# Sheet1-control.net
KiCad netlist of a schematic drawn in Altium Designer
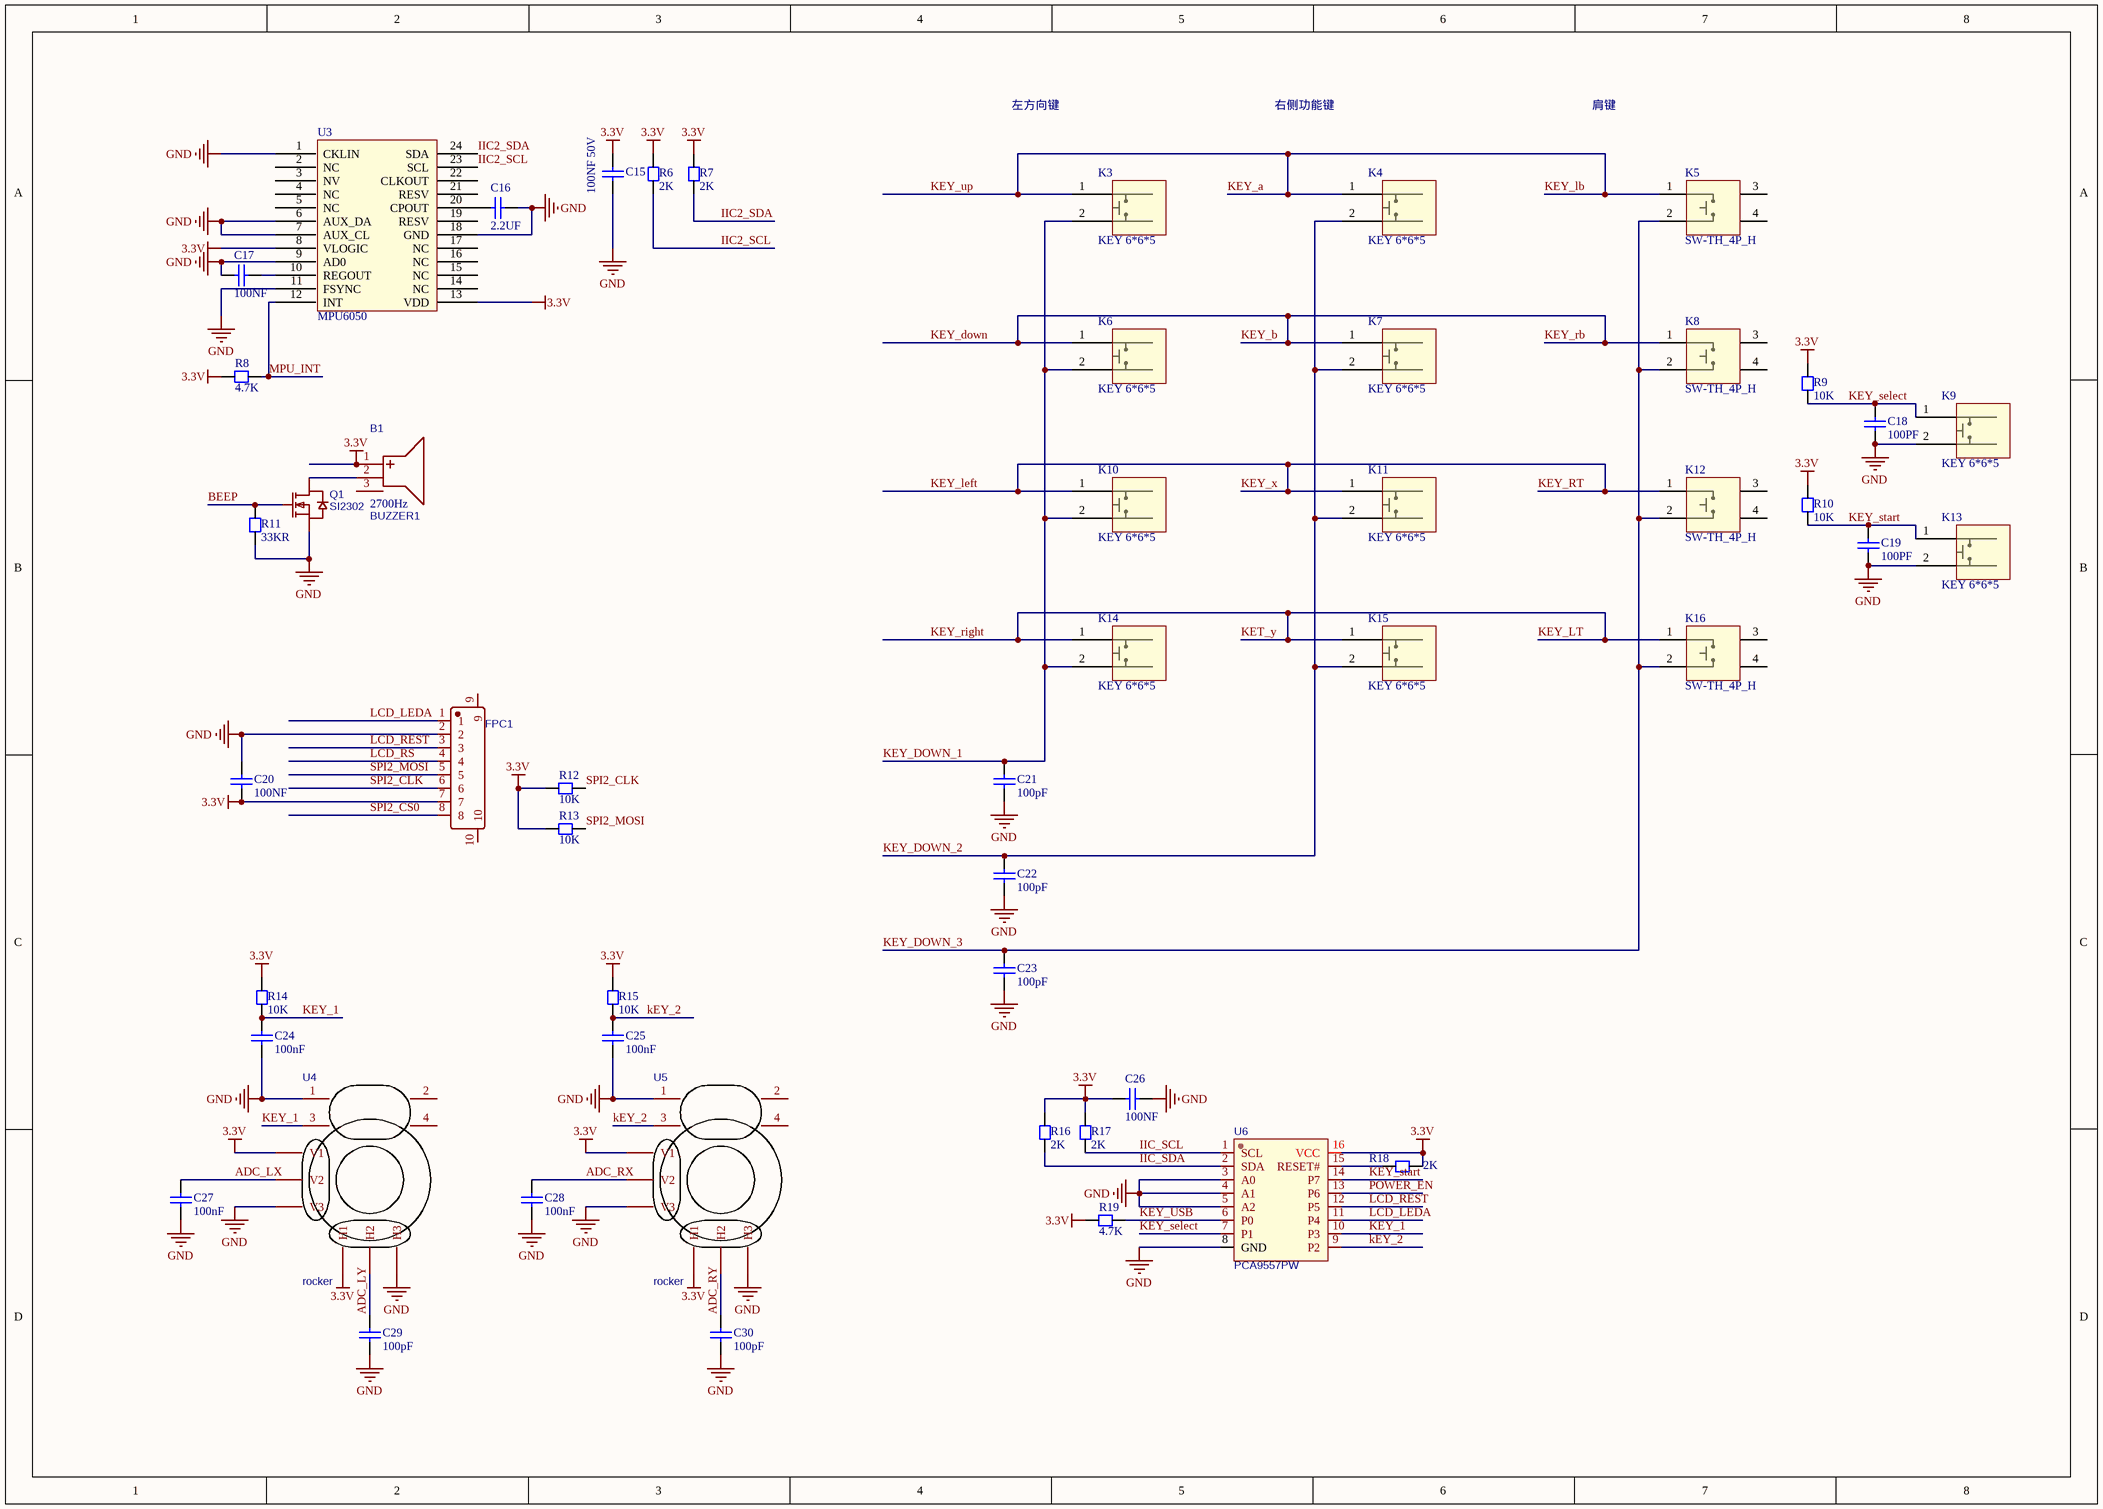
[diagram p0: Sheet1-control.SchDoc]

(export (version "E")
  (design (tool "Eeschema 10.0.6"))
  (components
    (comp (ref "B1")
      (value "BUZZER1")
      (footprint "BUZ-SMD_GSC7525RA")
      (description "2700Hz")
      (fields
        (field (name "MANUFACTURER") "INGHAi(赢海)")
        (field (name "MANUFACTURER PART") "GSC7525RA-16R2700")
        (field (name "CONTRIBUTOR") "LCSC")
      )
      (libsource (lib "base") (part "BUZZER1"))
    )
    (comp (ref "C15")
      (value "100NF 50V")
      (footprint "CC1608-0603")
      (description "0603封装的电容")
      (fields (field (name "PUBLISHER") "Altium Limited"))
      (libsource (lib "base") (part "Cap Chip 0603"))
    )
    (comp (ref "C16")
      (value "2.2UF")
      (footprint "CC1608-0603")
      (description "0603封装的电容")
      (fields (field (name "PUBLISHER") "Altium Limited"))
      (libsource (lib "base") (part "Cap Chip 0603"))
    )
    (comp (ref "C17")
      (value "100NF")
      (footprint "CC1608-0603")
      (description "0603封装的电容")
      (fields (field (name "PUBLISHER") "Altium Limited"))
      (libsource (lib "base") (part "Cap Chip 0603"))
    )
    (comp (ref "C18")
      (value "100PF")
      (footprint "CC1608-0603")
      (description "0603封装的电容")
      (fields (field (name "PUBLISHER") "Altium Limited"))
      (libsource (lib "base") (part "Cap Chip 0603"))
    )
    (comp (ref "C19")
      (value "100PF")
      (footprint "CC1608-0603")
      (description "0603封装的电容")
      (fields (field (name "PUBLISHER") "Altium Limited"))
      (libsource (lib "base") (part "Cap Chip 0603"))
    )
    (comp (ref "C20")
      (value "100NF")
      (footprint "CC1608-0603")
      (description "0603封装的电容")
      (fields (field (name "PUBLISHER") "Altium Limited"))
      (libsource (lib "base") (part "Cap Chip 0603"))
    )
    (comp (ref "C21")
      (value "100pF")
      (footprint "CC1608-0603")
      (description "0603封装的电容")
      (fields (field (name "PUBLISHER") "Altium Limited"))
      (libsource (lib "base") (part "Cap Chip 0603"))
    )
    (comp (ref "C22")
      (value "100pF")
      (footprint "CC1608-0603")
      (description "0603封装的电容")
      (fields (field (name "PUBLISHER") "Altium Limited"))
      (libsource (lib "base") (part "Cap Chip 0603"))
    )
    (comp (ref "C23")
      (value "100pF")
      (footprint "CC1608-0603")
      (description "0603封装的电容")
      (fields (field (name "PUBLISHER") "Altium Limited"))
      (libsource (lib "base") (part "Cap Chip 0603"))
    )
    (comp (ref "C24")
      (value "100nF")
      (footprint "CC1608-0603")
      (description "0603封装的电容")
      (fields (field (name "PUBLISHER") "Altium Limited"))
      (libsource (lib "base") (part "Cap Chip 0603"))
    )
    (comp (ref "C25")
      (value "100nF")
      (footprint "CC1608-0603")
      (description "0603封装的电容")
      (fields (field (name "PUBLISHER") "Altium Limited"))
      (libsource (lib "base") (part "Cap Chip 0603"))
    )
    (comp (ref "C26")
      (value "100NF")
      (footprint "CC1608-0603")
      (description "0603封装的电容")
      (fields (field (name "PUBLISHER") "Altium Limited"))
      (libsource (lib "base") (part "Cap Chip 0603"))
    )
    (comp (ref "C27")
      (value "100nF")
      (footprint "CC1608-0603")
      (description "0603封装的电容")
      (fields (field (name "PUBLISHER") "Altium Limited"))
      (libsource (lib "base") (part "Cap Chip 0603"))
    )
    (comp (ref "C28")
      (value "100nF")
      (footprint "CC1608-0603")
      (description "0603封装的电容")
      (fields (field (name "PUBLISHER") "Altium Limited"))
      (libsource (lib "base") (part "Cap Chip 0603"))
    )
    (comp (ref "C29")
      (value "100pF")
      (footprint "CC1608-0603")
      (description "0603封装的电容")
      (fields (field (name "PUBLISHER") "Altium Limited"))
      (libsource (lib "base") (part "Cap Chip 0603"))
    )
    (comp (ref "C30")
      (value "100pF")
      (footprint "CC1608-0603")
      (description "0603封装的电容")
      (fields (field (name "PUBLISHER") "Altium Limited"))
      (libsource (lib "base") (part "Cap Chip 0603"))
    )
    (comp (ref "FPC1")
      (value "FFC 05 8P")
      (footprint "FFC-SMD_8P-P0.50")
      (fields
        (field (name "MANUFACTURER") "TXGA(特思嘉)")
        (field (name "MANUFACTURER PART") "FFC05001-08SBB124W5M-H")
        (field (name "CONTRIBUTOR") "LCSC")
      )
      (libsource (lib "Connectors") (part "FFC 05 8P"))
    )
    (comp (ref "K3")
      (value "KEY 6*6*5")
      (footprint "KEY 6*6*5")
      (description "无声轻触开关")
      (libsource (lib "base") (part "KEY 6*6*5"))
    )
    (comp (ref "K4")
      (value "KEY 6*6*5")
      (footprint "KEY 6*6*5")
      (description "无声轻触开关")
      (libsource (lib "base") (part "KEY 6*6*5"))
    )
    (comp (ref "K5")
      (value "SW-TH_4P_H")
      (footprint "SW-TH_KH-6X6X7H-ZJ")
      (description "卧式轻触开关")
      (libsource (lib "base") (part "SW-TH_4P_H"))
    )
    (comp (ref "K6")
      (value "KEY 6*6*5")
      (footprint "KEY 6*6*5")
      (description "无声轻触开关")
      (libsource (lib "base") (part "KEY 6*6*5"))
    )
    (comp (ref "K7")
      (value "KEY 6*6*5")
      (footprint "KEY 6*6*5")
      (description "无声轻触开关")
      (libsource (lib "base") (part "KEY 6*6*5"))
    )
    (comp (ref "K8")
      (value "SW-TH_4P_H")
      (footprint "SW-TH_KH-6X6X7H-ZJ")
      (description "卧式轻触开关")
      (libsource (lib "base") (part "SW-TH_4P_H"))
    )
    (comp (ref "K9")
      (value "KEY 6*6*5")
      (footprint "KEY 6*6*5")
      (description "无声轻触开关")
      (libsource (lib "base") (part "KEY 6*6*5"))
    )
    (comp (ref "K10")
      (value "KEY 6*6*5")
      (footprint "KEY 6*6*5")
      (description "无声轻触开关")
      (libsource (lib "base") (part "KEY 6*6*5"))
    )
    (comp (ref "K11")
      (value "KEY 6*6*5")
      (footprint "KEY 6*6*5")
      (description "无声轻触开关")
      (libsource (lib "base") (part "KEY 6*6*5"))
    )
    (comp (ref "K12")
      (value "SW-TH_4P_H")
      (footprint "SW-TH_KH-6X6X7H-ZJ")
      (description "卧式轻触开关")
      (libsource (lib "base") (part "SW-TH_4P_H"))
    )
    (comp (ref "K13")
      (value "KEY 6*6*5")
      (footprint "KEY 6*6*5")
      (description "无声轻触开关")
      (libsource (lib "base") (part "KEY 6*6*5"))
    )
    (comp (ref "K14")
      (value "KEY 6*6*5")
      (footprint "KEY 6*6*5")
      (description "无声轻触开关")
      (libsource (lib "base") (part "KEY 6*6*5"))
    )
    (comp (ref "K15")
      (value "KEY 6*6*5")
      (footprint "KEY 6*6*5")
      (description "无声轻触开关")
      (libsource (lib "base") (part "KEY 6*6*5"))
    )
    (comp (ref "K16")
      (value "SW-TH_4P_H")
      (footprint "SW-TH_KH-6X6X7H-ZJ")
      (description "卧式轻触开关")
      (libsource (lib "base") (part "SW-TH_4P_H"))
    )
    (comp (ref "Q1")
      (value "SI2302")
      (footprint "SOT-23")
      (fields
        (field (name "MANUFACTURER") "TWGMC(台湾迪嘉)")
        (field (name "MANUFACTURER PART") "SI2306")
        (field (name "CONTRIBUTOR") "LCSC")
      )
      (libsource (lib "transistor") (part "SI2302"))
    )
    (comp (ref "R6")
      (value "2K")
      (footprint "CR1608-0603")
      (description "0603封装电阻")
      (fields (field (name "PUBLISHER") "Altium Limited"))
      (libsource (lib "") (part "Resistor Chip 0603_1"))
    )
    (comp (ref "R7")
      (value "2K")
      (footprint "CR1608-0603")
      (description "0603封装电阻")
      (fields (field (name "PUBLISHER") "Altium Limited"))
      (libsource (lib "") (part "Resistor Chip 0603_1"))
    )
    (comp (ref "R8")
      (value "4.7K")
      (footprint "CR1608-0603")
      (description "0603封装电阻")
      (fields (field (name "PUBLISHER") "Altium Limited"))
      (libsource (lib "") (part "Resistor Chip 0603_2"))
    )
    (comp (ref "R9")
      (value "10K")
      (footprint "CR1608-0603")
      (description "0603封装电阻")
      (fields (field (name "PUBLISHER") "Altium Limited"))
      (libsource (lib "") (part "Resistor Chip 0603_1"))
    )
    (comp (ref "R10")
      (value "10K")
      (footprint "CR1608-0603")
      (description "0603封装电阻")
      (fields (field (name "PUBLISHER") "Altium Limited"))
      (libsource (lib "") (part "Resistor Chip 0603_1"))
    )
    (comp (ref "R11")
      (value "33KR")
      (footprint "CR1608-0603")
      (description "贴片电阻")
      (libsource (lib "tianxiaohua_Schlib") (part "Chip resistor"))
    )
    (comp (ref "R12")
      (value "10K")
      (footprint "CR1608-0603")
      (description "0603封装电阻")
      (fields (field (name "PUBLISHER") "Altium Limited"))
      (libsource (lib "base") (part "Resistor Chip 0603"))
    )
    (comp (ref "R13")
      (value "10K")
      (footprint "CR1608-0603")
      (description "0603封装电阻")
      (fields (field (name "PUBLISHER") "Altium Limited"))
      (libsource (lib "base") (part "Resistor Chip 0603"))
    )
    (comp (ref "R14")
      (value "10K")
      (footprint "CR1608-0603")
      (description "0603封装电阻")
      (fields (field (name "PUBLISHER") "Altium Limited"))
      (libsource (lib "") (part "Resistor Chip 0603_3"))
    )
    (comp (ref "R15")
      (value "10K")
      (footprint "CR1608-0603")
      (description "0603封装电阻")
      (fields (field (name "PUBLISHER") "Altium Limited"))
      (libsource (lib "") (part "Resistor Chip 0603_3"))
    )
    (comp (ref "R16")
      (value "2K")
      (footprint "CR1608-0603")
      (description "0603封装电阻")
      (fields (field (name "PUBLISHER") "Altium Limited"))
      (libsource (lib "") (part "Resistor Chip 0603_1"))
    )
    (comp (ref "R17")
      (value "2K")
      (footprint "CR1608-0603")
      (description "0603封装电阻")
      (fields (field (name "PUBLISHER") "Altium Limited"))
      (libsource (lib "") (part "Resistor Chip 0603_1"))
    )
    (comp (ref "R18")
      (value "2K")
      (footprint "CR1608-0603")
      (description "0603封装电阻")
      (fields (field (name "PUBLISHER") "Altium Limited"))
      (libsource (lib "base") (part "Resistor Chip 0603"))
    )
    (comp (ref "R19")
      (value "4.7K")
      (footprint "CR1608-0603")
      (description "0603封装电阻")
      (fields (field (name "PUBLISHER") "Altium Limited"))
      (libsource (lib "") (part "Resistor Chip 0603_2"))
    )
    (comp (ref "U3")
      (value "MPU6050")
      (footprint "QFN24 - duplicate")
      (description "陀螺仪")
      (libsource (lib "sensor") (part "MPU6050"))
    )
    (comp (ref "U4")
      (value "rocker")
      (footprint "PCBComponent_1")
      (fields (field (name "MANUFACTURER PART") "摇杆") (field (name "CONTRIBUTOR") "Alex_Ai"))
      (libsource (lib "base") (part "rocker"))
    )
    (comp (ref "U5")
      (value "rocker")
      (footprint "PCBComponent_1")
      (fields (field (name "MANUFACTURER PART") "摇杆") (field (name "CONTRIBUTOR") "Alex_Ai"))
      (libsource (lib "base") (part "rocker"))
    )
    (comp (ref "U6")
      (value "PCA9557PW")
      (footprint "TSSOP-16")
      (description "TSSOP-16 8位I2C总线和SMBus I/O扩展器芯片")
      (fields (field (name "MANUFACTURER") "TI(德州仪器)") (field (name "CONTRIBUTOR") "LCSC"))
      (libsource (lib "PB-Chip") (part "PCA9557PW"))
    )
  )
  (nets
    (net (code "1") (name "/ADC_LX") (class "Default")
      (node (ref "C27") (pin "2") (pinfunction "2_2") (pintype "passive"))
      (node (ref "U4") (pin "6") (pinfunction "V2_6") (pintype "passive"))
    )
    (net (code "2") (name "/ADC_LY") (class "Default")
      (node (ref "C29") (pin "2") (pinfunction "2_2") (pintype "passive"))
      (node (ref "U4") (pin "9") (pinfunction "H2_9") (pintype "passive"))
    )
    (net (code "3") (name "/ADC_RX") (class "Default")
      (node (ref "C28") (pin "2") (pinfunction "2_2") (pintype "passive"))
      (node (ref "U5") (pin "6") (pinfunction "V2_6") (pintype "passive"))
    )
    (net (code "4") (name "/ADC_RY") (class "Default")
      (node (ref "C30") (pin "2") (pinfunction "2_2") (pintype "passive"))
      (node (ref "U5") (pin "9") (pinfunction "H2_9") (pintype "passive"))
    )
    (net (code "5") (name "/BEEP") (class "Default")
      (node (ref "Q1") (pin "1") (pinfunction "G_1") (pintype "passive"))
      (node (ref "R11") (pin "1") (pinfunction "1_1") (pintype "passive"))
    )
    (net (code "6") (name "/IIC2_SCL") (class "Default")
      (node (ref "R6") (pin "2") (pinfunction "2_2") (pintype "passive"))
      (node (ref "U3") (pin "23") (pinfunction "SCL_23") (pintype "passive"))
    )
    (net (code "7") (name "/IIC2_SDA") (class "Default")
      (node (ref "R7") (pin "2") (pinfunction "2_2") (pintype "passive"))
      (node (ref "U3") (pin "24") (pinfunction "SDA_24") (pintype "passive"))
    )
    (net (code "8") (name "/IIC_SCL") (class "Default")
      (node (ref "R17") (pin "2") (pinfunction "2_2") (pintype "passive"))
      (node (ref "U6") (pin "1") (pinfunction "SCL_1") (pintype "passive"))
    )
    (net (code "9") (name "/IIC_SDA") (class "Default")
      (node (ref "R16") (pin "2") (pinfunction "2_2") (pintype "passive"))
      (node (ref "U6") (pin "2") (pinfunction "SDA_2") (pintype "passive"))
    )
    (net (code "10") (name "/KET_y") (class "Default")
      (node (ref "K14") (pin "1") (pinfunction "1_1") (pintype "passive"))
      (node (ref "K15") (pin "1") (pinfunction "1_1") (pintype "passive"))
      (node (ref "K16") (pin "1") (pinfunction "1_1") (pintype "passive"))
    )
    (net (code "11") (name "/KEY_1") (class "Default")
      (node (ref "C24") (pin "2") (pinfunction "2_2") (pintype "passive"))
      (node (ref "R14") (pin "1") (pinfunction "1_1") (pintype "passive"))
      (node (ref "U4") (pin "3") (pinfunction "3_3") (pintype "passive"))
      (node (ref "U6") (pin "10") (pinfunction "P3_10") (pintype "passive"))
    )
    (net (code "12") (name "/KEY_DOWN_1") (class "Default")
      (node (ref "C21") (pin "2") (pinfunction "2_2") (pintype "passive"))
      (node (ref "K10") (pin "2") (pinfunction "2_2") (pintype "passive"))
      (node (ref "K14") (pin "2") (pinfunction "2_2") (pintype "passive"))
      (node (ref "K3") (pin "2") (pinfunction "2_2") (pintype "passive"))
      (node (ref "K6") (pin "2") (pinfunction "2_2") (pintype "passive"))
    )
    (net (code "13") (name "/KEY_DOWN_2") (class "Default")
      (node (ref "C22") (pin "2") (pinfunction "2_2") (pintype "passive"))
      (node (ref "K11") (pin "2") (pinfunction "2_2") (pintype "passive"))
      (node (ref "K15") (pin "2") (pinfunction "2_2") (pintype "passive"))
      (node (ref "K4") (pin "2") (pinfunction "2_2") (pintype "passive"))
      (node (ref "K7") (pin "2") (pinfunction "2_2") (pintype "passive"))
    )
    (net (code "14") (name "/KEY_DOWN_3") (class "Default")
      (node (ref "C23") (pin "2") (pinfunction "2_2") (pintype "passive"))
      (node (ref "K12") (pin "2") (pinfunction "2_2") (pintype "passive"))
      (node (ref "K16") (pin "2") (pinfunction "2_2") (pintype "passive"))
      (node (ref "K5") (pin "2") (pinfunction "2_2") (pintype "passive"))
      (node (ref "K8") (pin "2") (pinfunction "2_2") (pintype "passive"))
    )
    (net (code "15") (name "/KEY_RT") (class "Default")
      (node (ref "K10") (pin "1") (pinfunction "1_1") (pintype "passive"))
      (node (ref "K11") (pin "1") (pinfunction "1_1") (pintype "passive"))
      (node (ref "K12") (pin "1") (pinfunction "1_1") (pintype "passive"))
    )
    (net (code "16") (name "/KEY_USB") (class "Default")
      (node (ref "R19") (pin "2") (pinfunction "2_2") (pintype "passive"))
      (node (ref "U6") (pin "6") (pinfunction "P0_6") (pintype "passive"))
    )
    (net (code "17") (name "/KEY_a") (class "Default")
      (node (ref "K3") (pin "1") (pinfunction "1_1") (pintype "passive"))
      (node (ref "K4") (pin "1") (pinfunction "1_1") (pintype "passive"))
      (node (ref "K5") (pin "1") (pinfunction "1_1") (pintype "passive"))
    )
    (net (code "18") (name "/KEY_b") (class "Default")
      (node (ref "K6") (pin "1") (pinfunction "1_1") (pintype "passive"))
      (node (ref "K7") (pin "1") (pinfunction "1_1") (pintype "passive"))
      (node (ref "K8") (pin "1") (pinfunction "1_1") (pintype "passive"))
    )
    (net (code "19") (name "/KEY_select") (class "Default")
      (node (ref "C18") (pin "1") (pinfunction "1_1") (pintype "passive"))
      (node (ref "K9") (pin "1") (pinfunction "1_1") (pintype "passive"))
      (node (ref "R9") (pin "2") (pinfunction "2_2") (pintype "passive"))
      (node (ref "U6") (pin "7") (pinfunction "P1_7") (pintype "passive"))
    )
    (net (code "20") (name "/KEY_start") (class "Default")
      (node (ref "C19") (pin "1") (pinfunction "1_1") (pintype "passive"))
      (node (ref "K13") (pin "1") (pinfunction "1_1") (pintype "passive"))
      (node (ref "R10") (pin "2") (pinfunction "2_2") (pintype "passive"))
      (node (ref "U6") (pin "14") (pinfunction "P7_14") (pintype "passive"))
    )
    (net (code "21") (name "/LCD_LEDA") (class "Default")
      (node (ref "FPC1") (pin "1") (pinfunction "1_1") (pintype "passive"))
      (node (ref "U6") (pin "11") (pinfunction "P4_11") (pintype "passive"))
    )
    (net (code "22") (name "/LCD_REST") (class "Default")
      (node (ref "FPC1") (pin "3") (pinfunction "3_3") (pintype "passive"))
      (node (ref "U6") (pin "12") (pinfunction "P5_12") (pintype "passive"))
    )
    (net (code "23") (name "/LCD_RS") (class "Default")
      (node (ref "FPC1") (pin "4") (pinfunction "4_4") (pintype "passive"))
    )
    (net (code "24") (name "/MPU_INT") (class "Default")
      (node (ref "R8") (pin "2") (pinfunction "2_2") (pintype "passive"))
      (node (ref "U3") (pin "12") (pinfunction "INT_12") (pintype "passive"))
    )
    (net (code "25") (name "/POWER_EN") (class "Default")
      (node (ref "U6") (pin "13") (pinfunction "P6_13") (pintype "passive"))
    )
    (net (code "26") (name "/SPI2_CLK") (class "Default")
      (node (ref "FPC1") (pin "6") (pinfunction "6_6") (pintype "passive"))
      (node (ref "R12") (pin "1") (pinfunction "1_1") (pintype "passive"))
    )
    (net (code "27") (name "/SPI2_CS0") (class "Default")
      (node (ref "FPC1") (pin "8") (pinfunction "8_8") (pintype "passive"))
    )
    (net (code "28") (name "/SPI2_MOSI") (class "Default")
      (node (ref "FPC1") (pin "5") (pinfunction "5_5") (pintype "passive"))
      (node (ref "R13") (pin "1") (pinfunction "1_1") (pintype "passive"))
    )
    (net (code "29") (name "/kEY_2") (class "Default")
      (node (ref "C25") (pin "2") (pinfunction "2_2") (pintype "passive"))
      (node (ref "R15") (pin "1") (pinfunction "1_1") (pintype "passive"))
      (node (ref "U5") (pin "3") (pinfunction "3_3") (pintype "passive"))
      (node (ref "U6") (pin "9") (pinfunction "P2_9") (pintype "passive"))
    )
    (net (code "30") (name "3.3V") (class "Default")
      (node (ref "B1") (pin "1") (pinfunction "+_1") (pintype "passive"))
      (node (ref "C15") (pin "2") (pinfunction "2_2") (pintype "passive"))
      (node (ref "C20") (pin "1") (pinfunction "1_1") (pintype "passive"))
      (node (ref "C26") (pin "2") (pinfunction "2_2") (pintype "passive"))
      (node (ref "FPC1") (pin "7") (pinfunction "7_7") (pintype "passive"))
      (node (ref "R10") (pin "1") (pinfunction "1_1") (pintype "passive"))
      (node (ref "R12") (pin "2") (pinfunction "2_2") (pintype "passive"))
      (node (ref "R13") (pin "2") (pinfunction "2_2") (pintype "passive"))
      (node (ref "R14") (pin "2") (pinfunction "2_2") (pintype "passive"))
      (node (ref "R15") (pin "2") (pinfunction "2_2") (pintype "passive"))
      (node (ref "R16") (pin "1") (pinfunction "1_1") (pintype "passive"))
      (node (ref "R17") (pin "1") (pinfunction "1_1") (pintype "passive"))
      (node (ref "R18") (pin "1") (pinfunction "1_1") (pintype "passive"))
      (node (ref "R19") (pin "1") (pinfunction "1_1") (pintype "passive"))
      (node (ref "R6") (pin "1") (pinfunction "1_1") (pintype "passive"))
      (node (ref "R7") (pin "1") (pinfunction "1_1") (pintype "passive"))
      (node (ref "R8") (pin "1") (pinfunction "1_1") (pintype "passive"))
      (node (ref "R9") (pin "1") (pinfunction "1_1") (pintype "passive"))
      (node (ref "U3") (pin "13") (pinfunction "VDD_13") (pintype "passive"))
      (node (ref "U3") (pin "8") (pinfunction "VLOGIC_8") (pintype "passive"))
      (node (ref "U4") (pin "5") (pinfunction "V1_5") (pintype "passive"))
      (node (ref "U4") (pin "8") (pinfunction "H1_8") (pintype "passive"))
      (node (ref "U5") (pin "5") (pinfunction "V1_5") (pintype "passive"))
      (node (ref "U5") (pin "8") (pinfunction "H1_8") (pintype "passive"))
      (node (ref "U6") (pin "16") (pinfunction "VCC_16") (pintype "passive"))
    )
    (net (code "31") (name "GND") (class "Default")
      (node (ref "C15") (pin "1") (pinfunction "1_1") (pintype "passive"))
      (node (ref "C16") (pin "2") (pinfunction "2_2") (pintype "passive"))
      (node (ref "C17") (pin "1") (pinfunction "1_1") (pintype "passive"))
      (node (ref "C18") (pin "2") (pinfunction "2_2") (pintype "passive"))
      (node (ref "C19") (pin "2") (pinfunction "2_2") (pintype "passive"))
      (node (ref "C20") (pin "2") (pinfunction "2_2") (pintype "passive"))
      (node (ref "C21") (pin "1") (pinfunction "1_1") (pintype "passive"))
      (node (ref "C22") (pin "1") (pinfunction "1_1") (pintype "passive"))
      (node (ref "C23") (pin "1") (pinfunction "1_1") (pintype "passive"))
      (node (ref "C24") (pin "1") (pinfunction "1_1") (pintype "passive"))
      (node (ref "C25") (pin "1") (pinfunction "1_1") (pintype "passive"))
      (node (ref "C26") (pin "1") (pinfunction "1_1") (pintype "passive"))
      (node (ref "C27") (pin "1") (pinfunction "1_1") (pintype "passive"))
      (node (ref "C28") (pin "1") (pinfunction "1_1") (pintype "passive"))
      (node (ref "C29") (pin "1") (pinfunction "1_1") (pintype "passive"))
      (node (ref "C30") (pin "1") (pinfunction "1_1") (pintype "passive"))
      (node (ref "FPC1") (pin "2") (pinfunction "2_2") (pintype "passive"))
      (node (ref "K13") (pin "2") (pinfunction "2_2") (pintype "passive"))
      (node (ref "K9") (pin "2") (pinfunction "2_2") (pintype "passive"))
      (node (ref "Q1") (pin "2") (pinfunction "S_2") (pintype "passive"))
      (node (ref "R11") (pin "2") (pinfunction "2_2") (pintype "passive"))
      (node (ref "U3") (pin "1") (pinfunction "CKLIN_1") (pintype "passive"))
      (node (ref "U3") (pin "11") (pinfunction "FSYNC_11") (pintype "passive"))
      (node (ref "U3") (pin "18") (pinfunction "GND_18") (pintype "passive"))
      (node (ref "U3") (pin "6") (pinfunction "AUX_DA_6") (pintype "passive"))
      (node (ref "U3") (pin "7") (pinfunction "AUX_CL_7") (pintype "passive"))
      (node (ref "U3") (pin "9") (pinfunction "AD0_9") (pintype "passive"))
      (node (ref "U4") (pin "1") (pinfunction "1_1") (pintype "passive"))
      (node (ref "U4") (pin "10") (pinfunction "H3_10") (pintype "passive"))
      (node (ref "U4") (pin "7") (pinfunction "V3_7") (pintype "passive"))
      (node (ref "U5") (pin "1") (pinfunction "1_1") (pintype "passive"))
      (node (ref "U5") (pin "10") (pinfunction "H3_10") (pintype "passive"))
      (node (ref "U5") (pin "7") (pinfunction "V3_7") (pintype "passive"))
      (node (ref "U6") (pin "3") (pinfunction "A0_3") (pintype "passive"))
      (node (ref "U6") (pin "4") (pinfunction "A1_4") (pintype "passive"))
      (node (ref "U6") (pin "5") (pinfunction "A2_5") (pintype "passive"))
      (node (ref "U6") (pin "8") (pinfunction "GND_8") (pintype "passive"))
    )
    (net (code "32") (name "Net-(B1--)") (class "Default")
      (node (ref "B1") (pin "2") (pinfunction "-_2") (pintype "passive"))
      (node (ref "Q1") (pin "3") (pinfunction "D_3") (pintype "passive"))
    )
    (net (code "33") (name "Net-(U3-CPOUT)") (class "Default")
      (node (ref "C16") (pin "1") (pinfunction "1_1") (pintype "passive"))
      (node (ref "U3") (pin "20") (pinfunction "CPOUT_20") (pintype "passive"))
    )
    (net (code "34") (name "Net-(U3-REGOUT)") (class "Default")
      (node (ref "C17") (pin "2") (pinfunction "2_2") (pintype "passive"))
      (node (ref "U3") (pin "10") (pinfunction "REGOUT_10") (pintype "passive"))
    )
    (net (code "35") (name "Net-(U6-RESET#)") (class "Default")
      (node (ref "R18") (pin "2") (pinfunction "2_2") (pintype "passive"))
      (node (ref "U6") (pin "15") (pinfunction "RESET#_15") (pintype "passive"))
    )
    (net (code "36") (name "unconnected-(B1-EH-Pad3)") (class "Default")
      (node (ref "B1") (pin "3") (pinfunction "EH_3") (pintype "passive"))
    )
    (net (code "37") (name "unconnected-(FPC1-Pad9)") (class "Default")
      (node (ref "FPC1") (pin "9") (pinfunction "9_9") (pintype "passive"))
    )
    (net (code "38") (name "unconnected-(FPC1-Pad10)") (class "Default")
      (node (ref "FPC1") (pin "10") (pinfunction "10_10") (pintype "passive"))
    )
    (net (code "39") (name "unconnected-(K5-Pad3)") (class "Default")
      (node (ref "K5") (pin "3") (pinfunction "3_3") (pintype "passive"))
    )
    (net (code "40") (name "unconnected-(K5-Pad4)") (class "Default")
      (node (ref "K5") (pin "4") (pinfunction "4_4") (pintype "passive"))
    )
    (net (code "41") (name "unconnected-(K8-Pad3)") (class "Default")
      (node (ref "K8") (pin "3") (pinfunction "3_3") (pintype "passive"))
    )
    (net (code "42") (name "unconnected-(K8-Pad4)") (class "Default")
      (node (ref "K8") (pin "4") (pinfunction "4_4") (pintype "passive"))
    )
    (net (code "43") (name "unconnected-(K12-Pad3)") (class "Default")
      (node (ref "K12") (pin "3") (pinfunction "3_3") (pintype "passive"))
    )
    (net (code "44") (name "unconnected-(K12-Pad4)") (class "Default")
      (node (ref "K12") (pin "4") (pinfunction "4_4") (pintype "passive"))
    )
    (net (code "45") (name "unconnected-(K16-Pad3)") (class "Default")
      (node (ref "K16") (pin "3") (pinfunction "3_3") (pintype "passive"))
    )
    (net (code "46") (name "unconnected-(K16-Pad4)") (class "Default")
      (node (ref "K16") (pin "4") (pinfunction "4_4") (pintype "passive"))
    )
    (net (code "47") (name "unconnected-(U3-CLKOUT-Pad22)") (class "Default")
      (node (ref "U3") (pin "22") (pinfunction "CLKOUT_22") (pintype "passive"))
    )
    (net (code "48") (name "unconnected-(U3-NC-Pad2)") (class "Default")
      (node (ref "U3") (pin "2") (pinfunction "NC_2") (pintype "passive"))
    )
    (net (code "49") (name "unconnected-(U3-NC-Pad4)") (class "Default")
      (node (ref "U3") (pin "4") (pinfunction "NC_4") (pintype "passive"))
    )
    (net (code "50") (name "unconnected-(U3-NC-Pad5)") (class "Default")
      (node (ref "U3") (pin "5") (pinfunction "NC_5") (pintype "passive"))
    )
    (net (code "51") (name "unconnected-(U3-NC-Pad14)") (class "Default")
      (node (ref "U3") (pin "14") (pinfunction "NC_14") (pintype "passive"))
    )
    (net (code "52") (name "unconnected-(U3-NC-Pad15)") (class "Default")
      (node (ref "U3") (pin "15") (pinfunction "NC_15") (pintype "passive"))
    )
    (net (code "53") (name "unconnected-(U3-NC-Pad16)") (class "Default")
      (node (ref "U3") (pin "16") (pinfunction "NC_16") (pintype "passive"))
    )
    (net (code "54") (name "unconnected-(U3-NC-Pad17)") (class "Default")
      (node (ref "U3") (pin "17") (pinfunction "NC_17") (pintype "passive"))
    )
    (net (code "55") (name "unconnected-(U3-NV-Pad3)") (class "Default")
      (node (ref "U3") (pin "3") (pinfunction "NV_3") (pintype "passive"))
    )
    (net (code "56") (name "unconnected-(U3-RESV-Pad19)") (class "Default")
      (node (ref "U3") (pin "19") (pinfunction "RESV_19") (pintype "passive"))
    )
    (net (code "57") (name "unconnected-(U3-RESV-Pad21)") (class "Default")
      (node (ref "U3") (pin "21") (pinfunction "RESV_21") (pintype "passive"))
    )
    (net (code "58") (name "unconnected-(U4-Pad2)") (class "Default")
      (node (ref "U4") (pin "2") (pinfunction "2_2") (pintype "passive"))
    )
    (net (code "59") (name "unconnected-(U4-Pad4)") (class "Default")
      (node (ref "U4") (pin "4") (pinfunction "4_4") (pintype "passive"))
    )
    (net (code "60") (name "unconnected-(U5-Pad2)") (class "Default")
      (node (ref "U5") (pin "2") (pinfunction "2_2") (pintype "passive"))
    )
    (net (code "61") (name "unconnected-(U5-Pad4)") (class "Default")
      (node (ref "U5") (pin "4") (pinfunction "4_4") (pintype "passive"))
    )
  )
)
